# OSHChip_CMSIS_DAP_V1_0.net
KiCad netlist of a schematic drawn in Altium Designer
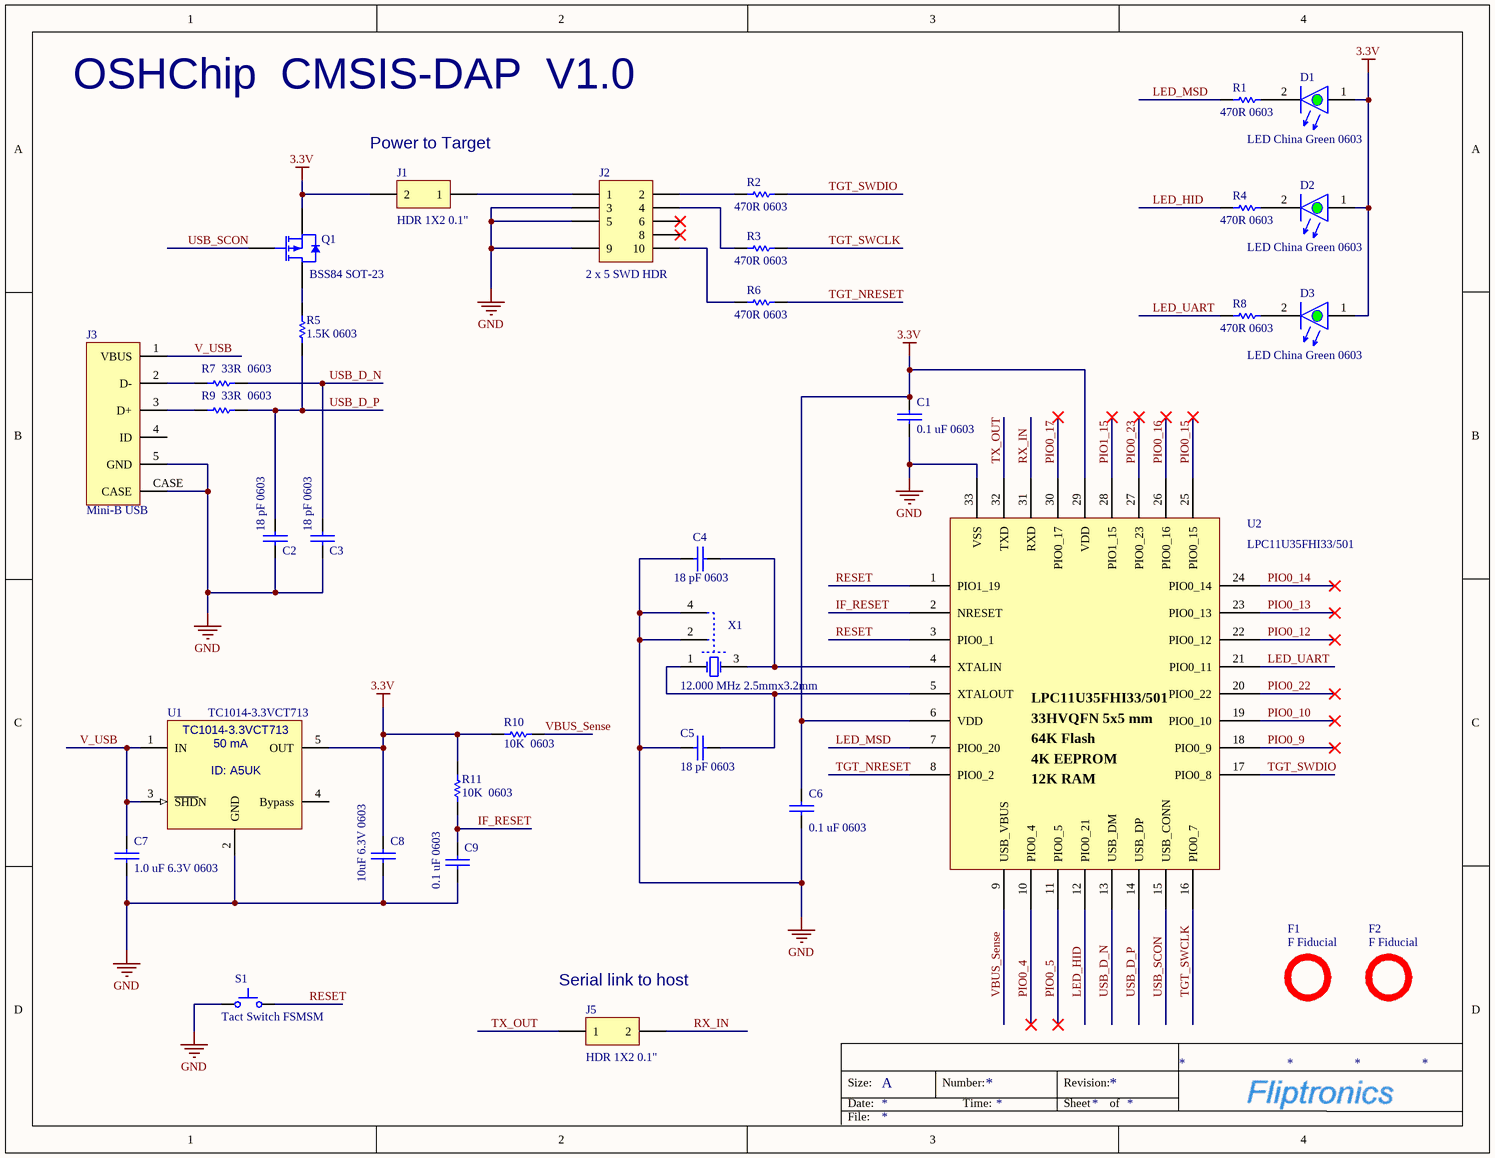
[diagram p0: OSHChip_CMSIS_DAP_V1.0.SchDoc]

(export (version "E")
  (design (tool "Eeschema 10.0.6"))
  (components
    (comp (ref "C1")
      (value "0.1 uF 0603")
      (footprint "Footprints:0603 Cap")
      (description "0.1 uF 16V 10% X7R 0603")
      (fields
        (field (name "PART NUMBER") "CC0603KRX7R7BB104")
        (field (name "LATESTREVISIONNOTE") "Created by PMF")
      )
      (libsource (lib "OSHChip_V1.0") (part "C 0.1 uF 16V 10% X7R 0603"))
    )
    (comp (ref "C2")
      (value "18 pF 0603")
      (footprint "Footprints:0603 Cap")
      (description "Capacitor 18 pF 0603  50V  NP0  5%")
      (fields
        (field (name "PART NUMBER") "CL10C180JB8NNNC")
        (field (name "LATESTREVISIONNOTE") "Created by PMF")
      )
      (libsource (lib "OSHChip_V1.0") (part "C 18 pF 0603  50V  NP0  5%"))
    )
    (comp (ref "C3")
      (value "18 pF 0603")
      (footprint "Footprints:0603 Cap")
      (description "Capacitor 18 pF 0603  50V  NP0  5%")
      (fields
        (field (name "PART NUMBER") "CL10C180JB8NNNC")
        (field (name "LATESTREVISIONNOTE") "Created by PMF")
      )
      (libsource (lib "OSHChip_V1.0") (part "C 18 pF 0603  50V  NP0  5%"))
    )
    (comp (ref "C4")
      (value "18 pF 0603")
      (footprint "Footprints:0603 Cap")
      (description "Capacitor 18 pF 0603  50V  NP0  5%")
      (fields
        (field (name "PART NUMBER") "CL10C180JB8NNNC")
        (field (name "LATESTREVISIONNOTE") "Created by PMF")
      )
      (libsource (lib "OSHChip_V1.0") (part "C 18 pF 0603  50V  NP0  5%"))
    )
    (comp (ref "C5")
      (value "18 pF 0603")
      (footprint "Footprints:0603 Cap")
      (description "Capacitor 18 pF 0603  50V  NP0  5%")
      (fields
        (field (name "PART NUMBER") "CL10C180JB8NNNC")
        (field (name "LATESTREVISIONNOTE") "Created by PMF")
      )
      (libsource (lib "OSHChip_V1.0") (part "C 18 pF 0603  50V  NP0  5%"))
    )
    (comp (ref "C6")
      (value "0.1 uF 0603")
      (footprint "Footprints:0603 Cap")
      (description "0.1 uF 16V 10% X7R 0603")
      (fields
        (field (name "PART NUMBER") "CC0603KRX7R7BB104")
        (field (name "LATESTREVISIONNOTE") "Created by PMF")
      )
      (libsource (lib "OSHChip_V1.0") (part "C 0.1 uF 16V 10% X7R 0603"))
    )
    (comp (ref "C7")
      (value "1.0 uF 6.3V 0603")
      (footprint "Footprints:0603 Cap")
      (description "Capacitor 1.0 uF 6.3V 10% X7R 0603")
      (fields
        (field (name "PART NUMBER") "CL10B105KQ8NNNC")
        (field (name "LATESTREVISIONNOTE") "Created by PMF")
      )
      (libsource (lib "OSHChip_V1.0") (part "C 1.0 uF 6.3V 10% X7R 0603"))
    )
    (comp (ref "C8")
      (value "10uF 6.3V 0603")
      (footprint "Footprints:0603 Cap")
      (description "Capacitor 10uF 0603 6.3V 20% X5R")
      (fields
        (field (name "PART NUMBER") "CL10A106MQ8NNNC")
        (field (name "LATESTREVISIONNOTE") "Created by PMF")
      )
      (libsource (lib "OSHChip_V1.0") (part "C 10uF 0603 6.3V 20% X5R"))
    )
    (comp (ref "C9")
      (value "0.1 uF 0603")
      (footprint "Footprints:0603 Cap")
      (description "0.1 uF 16V 10% X7R 0603")
      (fields
        (field (name "PART NUMBER") "CC0603KRX7R7BB104")
        (field (name "LATESTREVISIONNOTE") "Created by PMF")
      )
      (libsource (lib "OSHChip_V1.0") (part "C 0.1 uF 16V 10% X7R 0603"))
    )
    (comp (ref "D1")
      (value "LED China Green 0603")
      (footprint "0603_LED")
      (description "LED Green 0603")
      (fields
        (field (name "PART NUMBER") "ChinaLED_Green")
        (field (name "LATESTREVISIONNOTE") "Created by PMF")
      )
      (libsource (lib "OSHChip_V1.0") (part "D LED LED_China_Green_0603"))
    )
    (comp (ref "D2")
      (value "LED China Green 0603")
      (footprint "0603_LED")
      (description "LED Green 0603")
      (fields
        (field (name "PART NUMBER") "ChinaLED_Green")
        (field (name "LATESTREVISIONNOTE") "Created by PMF")
      )
      (libsource (lib "OSHChip_V1.0") (part "D LED LED_China_Green_0603"))
    )
    (comp (ref "D3")
      (value "LED China Green 0603")
      (footprint "0603_LED")
      (description "LED Green 0603")
      (fields
        (field (name "PART NUMBER") "ChinaLED_Green")
        (field (name "LATESTREVISIONNOTE") "Created by PMF")
      )
      (libsource (lib "OSHChip_V1.0") (part "D LED LED_China_Green_0603"))
    )
    (comp (ref "F1")
      (value "F Fiducial")
      (footprint "footprints:Fiducial Dot")
      (description "Fiducial")
      (fields
        (field (name "1 MANUFACTURE A PART NUMBER") "PCB_Artwork")
        (field (name "LATESTREVISIONNOTE") "Created by PMF")
        (field (name "PUBLISHER") "Fliptronics")
      )
      (libsource (lib "*") (part "F Fiducial"))
    )
    (comp (ref "F2")
      (value "F Fiducial")
      (footprint "footprints:Fiducial Dot")
      (description "Fiducial")
      (fields
        (field (name "1 MANUFACTURE A PART NUMBER") "PCB_Artwork")
        (field (name "LATESTREVISIONNOTE") "Created by PMF")
        (field (name "PUBLISHER") "Fliptronics")
      )
      (libsource (lib "*") (part "F Fiducial"))
    )
    (comp (ref "J1")
      (value "HDR 1X2 0.1\"")
      (footprint "HDR_2X1_2MM54")
      (description "Header 1X2, 2.54 mm pitch")
      (fields (field (name "PART NUMBER") "M20-9990246") (field (name "LATESTREVISIONNOTE") "Created by PMF"))
      (libsource (lib "") (part "J Header 1X2, 2.54 mm pitch_1"))
    )
    (comp (ref "J2")
      (value "2 x 5 SWD HDR")
      (footprint "Footprints:HDR_2x5_1.27mm-Through_Hole_SWD No Shroud")
      (description "FTSH-105-01-L-D through hole, No Key, No shroud")
      (fields
        (field (name "PART NUMBER") "FTSH-105-01-L-D")
        (field (name "LATESTREVISIONNOTE") "Created by PMF")
      )
      (libsource (lib "OSHChip_V1.0") (part "J Header 5X2 J-Link Lite   FTSH-105-01-L-D through hole, No Key, No shroud"))
    )
    (comp (ref "J3")
      (value "Mini-B USB")
      (footprint "footprints:USB_Mini-B")
      (description "USB 2.0, Right Angle, SMT, B Type, Receptacle, 5 Position, Black")
      (fields
        (field (name "PART NUMBER") "690-005-299-043")
        (field (name "LATESTREVISIONNOTE") "Created by PMF")
      )
      (libsource (lib "OSHChip_V1.0") (part "J Mini-B USB 690-005-299-043 With alignment pins"))
    )
    (comp (ref "J5")
      (value "HDR 1X2 0.1\"")
      (footprint "HDR_2X1_2MM54")
      (description "Header 1X2, 2.54 mm pitch")
      (fields (field (name "PART NUMBER") "M20-9990246") (field (name "LATESTREVISIONNOTE") "Created by PMF"))
      (libsource (lib "OSHChip_V1.0") (part "J Header 1X2, 2.54 mm pitch"))
    )
    (comp (ref "Q1")
      (value "BSS84 SOT-23")
      (footprint "Footprints:SOT23-123")
      (description "P-channel Enhancement Mode Vertical D-MOSFET")
      (fields (field (name "PART NUMBER") "BSS84,215"))
      (libsource (lib "OSHChip_V1.0") (part "Q BSS84"))
    )
    (comp (ref "R1")
      (value "470R 0603")
      (footprint "Footprints:0603 Res")
      (description "Resistor 470R 0603 1/10 W 1%")
      (fields
        (field (name "PART NUMBER") "RC1608F471CS")
        (field (name "LATESTREVISIONNOTE") "Created by PMF")
      )
      (libsource (lib "OSHChip_V1.0") (part "R 470R 0603 1/10 W 1%"))
    )
    (comp (ref "R2")
      (value "470R 0603")
      (footprint "Footprints:0603 Res")
      (description "Resistor 470R 0603 1/10 W 1%")
      (fields
        (field (name "PART NUMBER") "RC1608F471CS")
        (field (name "LATESTREVISIONNOTE") "Created by PMF")
      )
      (libsource (lib "OSHChip_V1.0") (part "R 470R 0603 1/10 W 1%"))
    )
    (comp (ref "R3")
      (value "470R 0603")
      (footprint "Footprints:0603 Res")
      (description "Resistor 470R 0603 1/10 W 1%")
      (fields
        (field (name "PART NUMBER") "RC1608F471CS")
        (field (name "LATESTREVISIONNOTE") "Created by PMF")
      )
      (libsource (lib "OSHChip_V1.0") (part "R 470R 0603 1/10 W 1%"))
    )
    (comp (ref "R4")
      (value "470R 0603")
      (footprint "Footprints:0603 Res")
      (description "Resistor 470R 0603 1/10 W 1%")
      (fields
        (field (name "PART NUMBER") "RC1608F471CS")
        (field (name "LATESTREVISIONNOTE") "Created by PMF")
      )
      (libsource (lib "OSHChip_V1.0") (part "R 470R 0603 1/10 W 1%"))
    )
    (comp (ref "R5")
      (value "1.5K 0603")
      (footprint "Footprints:0603 Res")
      (description "Resistor 1.5K 0402 1/10 W 1%")
      (fields
        (field (name "PART NUMBER") "RC0603FR-071K5L")
        (field (name "LATESTREVISIONNOTE") "Created by PMF")
      )
      (libsource (lib "OSHChip_V1.0") (part "R 1.5K 0603 1/10 W 1%"))
    )
    (comp (ref "R6")
      (value "470R 0603")
      (footprint "Footprints:0603 Res")
      (description "Resistor 470R 0603 1/10 W 1%")
      (fields
        (field (name "PART NUMBER") "RC1608F471CS")
        (field (name "LATESTREVISIONNOTE") "Created by PMF")
      )
      (libsource (lib "OSHChip_V1.0") (part "R 470R 0603 1/10 W 1%"))
    )
    (comp (ref "R7")
      (value "33R  0603")
      (footprint "Footprints:0603 Res")
      (description "Resistor 33R 0603 1/10 W 1%")
      (fields
        (field (name "PART NUMBER") "MCR03ERTF33R0")
        (field (name "LATESTREVISIONNOTE") "Created by PMF")
      )
      (libsource (lib "OSHChip_V1.0") (part "R 33R 0603 1/10 W 1%"))
    )
    (comp (ref "R8")
      (value "470R 0603")
      (footprint "Footprints:0603 Res")
      (description "Resistor 470R 0603 1/10 W 1%")
      (fields
        (field (name "PART NUMBER") "RC1608F471CS")
        (field (name "LATESTREVISIONNOTE") "Created by PMF")
      )
      (libsource (lib "OSHChip_V1.0") (part "R 470R 0603 1/10 W 1%"))
    )
    (comp (ref "R9")
      (value "33R  0603")
      (footprint "Footprints:0603 Res")
      (description "Resistor 33R 0603 1/10 W 1%")
      (fields
        (field (name "PART NUMBER") "MCR03ERTF33R0")
        (field (name "LATESTREVISIONNOTE") "Created by PMF")
      )
      (libsource (lib "OSHChip_V1.0") (part "R 33R 0603 1/10 W 1%"))
    )
    (comp (ref "R10")
      (value "10K  0603")
      (footprint "Footprints:0603 Res")
      (description "Resistor 10K 0603 1/10 W 1%")
      (fields
        (field (name "PART NUMBER") "MCR03ERTF1002")
        (field (name "LATESTREVISIONNOTE") "Created by PMF")
      )
      (libsource (lib "OSHChip_V1.0") (part "R 10K 0603 1/10 W 1%"))
    )
    (comp (ref "R11")
      (value "10K  0603")
      (footprint "Footprints:0603 Res")
      (description "Resistor 10K 0603 1/10 W 1%")
      (fields
        (field (name "PART NUMBER") "MCR03ERTF1002")
        (field (name "LATESTREVISIONNOTE") "Created by PMF")
      )
      (libsource (lib "OSHChip_V1.0") (part "R 10K 0603 1/10 W 1%"))
    )
    (comp (ref "S1")
      (value "Tact Switch FSMSM")
      (footprint "Footprints:FSMSM Tact Switch")
      (description "6 x 3.5 mm   Tact Switch")
      (fields (field (name "PART NUMBER") "FSMSMTR") (field (name "LATESTREVISIONNOTE") "Created by PMF"))
      (libsource (lib "OSHChip_V1.0") (part "S FSMSM 6 x 3.5 mm   Tact Switch"))
    )
    (comp (ref "U1")
      (value "TC1014-3.3VCT713")
      (footprint "Footprints:SOT23-5AL")
      (description "3.3V 50mA LDO")
      (fields (field (name "LATESTREVISIONNOTE") "Created by PMF"))
      (libsource (lib "OSHChip_V1.0") (part "U TC1014-3.3VCT713"))
    )
    (comp (ref "U2")
      (value "LPC11U35FHI33/501")
      (footprint "Footprints:LPC11U35 QFN32 footprint")
      (description "LPC11U35FHI33/501 ARM M0 64KB FLASH 33HVQFN")
      (fields (field (name "LATESTREVISIONNOTE") "Created by PMF"))
      (libsource (lib "OSHChip_V1.0") (part "U LPC11U35FHI33/501"))
    )
    (comp (ref "X1")
      (value "12.000 MHz 2.5mmx3.2mm")
      (footprint "footprints:NX3225SA - High Density")
      (description "12MHz")
      (fields
        (field (name "PART NUMBER") "CX3225GB12000D0HEQCC")
        (field (name "LATESTREVISIONNOTE") "Created by PMF")
      )
      (libsource (lib "OSHChip_V1.0") (part "X 12MHz, 2.5mmx3.2mm 30ppm 8 pF"))
    )
  )
  (nets
    (net (code "1") (name "/IF_RESET") (class "Default")
      (node (ref "C9") (pin "2") (pinfunction "2_2") (pintype "passive"))
      (node (ref "R11") (pin "1") (pinfunction "1_1") (pintype "passive"))
      (node (ref "U2") (pin "2") (pinfunction "NRESET_2") (pintype "passive"))
    )
    (net (code "2") (name "/LED_HID") (class "Default")
      (node (ref "R4") (pin "1") (pinfunction "1_1") (pintype "passive"))
      (node (ref "U2") (pin "12") (pinfunction "PIO0_21_12") (pintype "passive"))
    )
    (net (code "3") (name "/LED_MSD") (class "Default")
      (node (ref "R1") (pin "1") (pinfunction "1_1") (pintype "passive"))
      (node (ref "U2") (pin "7") (pinfunction "PIO0_20_7") (pintype "passive"))
    )
    (net (code "4") (name "/LED_UART") (class "Default")
      (node (ref "R8") (pin "1") (pinfunction "1_1") (pintype "passive"))
      (node (ref "U2") (pin "21") (pinfunction "PIO0_11_21") (pintype "passive"))
    )
    (net (code "5") (name "/PIO0_4") (class "Default")
      (node (ref "U2") (pin "10") (pinfunction "PIO0_4_10") (pintype "passive+no_connect"))
    )
    (net (code "6") (name "/PIO0_5") (class "Default")
      (node (ref "U2") (pin "11") (pinfunction "PIO0_5_11") (pintype "passive+no_connect"))
    )
    (net (code "7") (name "/PIO0_9") (class "Default")
      (node (ref "U2") (pin "18") (pinfunction "PIO0_9_18") (pintype "passive+no_connect"))
    )
    (net (code "8") (name "/PIO0_10") (class "Default")
      (node (ref "U2") (pin "19") (pinfunction "PIO0_10_19") (pintype "passive+no_connect"))
    )
    (net (code "9") (name "/PIO0_12") (class "Default")
      (node (ref "U2") (pin "22") (pinfunction "PIO0_12_22") (pintype "passive+no_connect"))
    )
    (net (code "10") (name "/PIO0_13") (class "Default")
      (node (ref "U2") (pin "23") (pinfunction "PIO0_13_23") (pintype "passive+no_connect"))
    )
    (net (code "11") (name "/PIO0_14") (class "Default")
      (node (ref "U2") (pin "24") (pinfunction "PIO0_14_24") (pintype "passive+no_connect"))
    )
    (net (code "12") (name "/PIO0_15") (class "Default")
      (node (ref "U2") (pin "25") (pinfunction "PIO0_15_25") (pintype "passive+no_connect"))
    )
    (net (code "13") (name "/PIO0_16") (class "Default")
      (node (ref "U2") (pin "26") (pinfunction "PIO0_16_26") (pintype "passive+no_connect"))
    )
    (net (code "14") (name "/PIO0_17") (class "Default")
      (node (ref "U2") (pin "30") (pinfunction "PIO0_17_30") (pintype "passive+no_connect"))
    )
    (net (code "15") (name "/PIO0_22") (class "Default")
      (node (ref "U2") (pin "20") (pinfunction "PIO0_22_20") (pintype "passive+no_connect"))
    )
    (net (code "16") (name "/PIO0_23") (class "Default")
      (node (ref "U2") (pin "27") (pinfunction "PIO0_23_27") (pintype "passive+no_connect"))
    )
    (net (code "17") (name "/PIO1_15") (class "Default")
      (node (ref "U2") (pin "28") (pinfunction "PIO1_15_28") (pintype "passive+no_connect"))
    )
    (net (code "18") (name "/RESET") (class "Default")
      (node (ref "S1") (pin "2") (pinfunction "2_2") (pintype "passive"))
      (node (ref "U2") (pin "1") (pinfunction "PIO1_19_1") (pintype "passive"))
      (node (ref "U2") (pin "3") (pinfunction "PIO0_1_3") (pintype "passive"))
    )
    (net (code "19") (name "/RX_IN") (class "Default")
      (node (ref "J5") (pin "2") (pinfunction "2_2") (pintype "passive"))
      (node (ref "U2") (pin "31") (pinfunction "RXD_31") (pintype "passive"))
    )
    (net (code "20") (name "/TGT_NRESET") (class "Default")
      (node (ref "R6") (pin "2") (pinfunction "2_2") (pintype "passive"))
      (node (ref "U2") (pin "8") (pinfunction "PIO0_2_8") (pintype "passive"))
    )
    (net (code "21") (name "/TGT_SWCLK") (class "Default")
      (node (ref "R3") (pin "2") (pinfunction "2_2") (pintype "passive"))
      (node (ref "U2") (pin "16") (pinfunction "PIO0_7_16") (pintype "passive"))
    )
    (net (code "22") (name "/TGT_SWDIO") (class "Default")
      (node (ref "R2") (pin "2") (pinfunction "2_2") (pintype "passive"))
      (node (ref "U2") (pin "17") (pinfunction "PIO0_8_17") (pintype "passive"))
    )
    (net (code "23") (name "/TX_OUT") (class "Default")
      (node (ref "J5") (pin "1") (pinfunction "1_1") (pintype "passive"))
      (node (ref "U2") (pin "32") (pinfunction "TXD_32") (pintype "passive"))
    )
    (net (code "24") (name "/USB_D_N") (class "Default")
      (node (ref "C3") (pin "2") (pinfunction "2_2") (pintype "passive"))
      (node (ref "R7") (pin "2") (pinfunction "2_2") (pintype "passive"))
      (node (ref "U2") (pin "13") (pinfunction "USB_DM_13") (pintype "passive"))
    )
    (net (code "25") (name "/USB_D_P") (class "Default")
      (node (ref "C2") (pin "2") (pinfunction "2_2") (pintype "passive"))
      (node (ref "R5") (pin "1") (pinfunction "1_1") (pintype "passive"))
      (node (ref "R9") (pin "2") (pinfunction "2_2") (pintype "passive"))
      (node (ref "U2") (pin "14") (pinfunction "USB_DP_14") (pintype "passive"))
    )
    (net (code "26") (name "/USB_SCON") (class "Default")
      (node (ref "Q1") (pin "1") (pinfunction "G_1") (pintype "passive"))
      (node (ref "U2") (pin "15") (pinfunction "USB_CONN_15") (pintype "passive"))
    )
    (net (code "27") (name "/VBUS_Sense") (class "Default")
      (node (ref "R10") (pin "1") (pinfunction "1_1") (pintype "passive"))
      (node (ref "U2") (pin "9") (pinfunction "USB_VBUS_9") (pintype "passive"))
    )
    (net (code "28") (name "/V_USB") (class "Default")
      (node (ref "C7") (pin "2") (pinfunction "2_2") (pintype "passive"))
      (node (ref "J3") (pin "1") (pinfunction "VBUS_1") (pintype "power_in"))
      (node (ref "U1") (pin "1") (pinfunction "IN_1") (pintype "power_in"))
      (node (ref "U1") (pin "3") (pinfunction "~{SHD}N_3") (pintype "input"))
    )
    (net (code "29") (name "3.3V") (class "Default")
      (node (ref "C1") (pin "2") (pinfunction "2_2") (pintype "passive"))
      (node (ref "C6") (pin "2") (pinfunction "2_2") (pintype "passive"))
      (node (ref "C8") (pin "2") (pinfunction "2_2") (pintype "passive"))
      (node (ref "D1") (pin "1") (pinfunction "1_1") (pintype "passive"))
      (node (ref "D2") (pin "1") (pinfunction "1_1") (pintype "passive"))
      (node (ref "D3") (pin "1") (pinfunction "1_1") (pintype "passive"))
      (node (ref "J1") (pin "2") (pinfunction "2_2") (pintype "passive"))
      (node (ref "Q1") (pin "2") (pinfunction "S_2") (pintype "passive"))
      (node (ref "R10") (pin "2") (pinfunction "2_2") (pintype "passive"))
      (node (ref "R11") (pin "2") (pinfunction "2_2") (pintype "passive"))
      (node (ref "U1") (pin "5") (pinfunction "OUT_5") (pintype "power_in"))
      (node (ref "U2") (pin "29") (pinfunction "VDD_29") (pintype "passive"))
      (node (ref "U2") (pin "6") (pinfunction "VDD_6") (pintype "passive"))
    )
    (net (code "30") (name "GND") (class "Default")
      (node (ref "C1") (pin "1") (pinfunction "1_1") (pintype "passive"))
      (node (ref "C2") (pin "1") (pinfunction "1_1") (pintype "passive"))
      (node (ref "C3") (pin "1") (pinfunction "1_1") (pintype "passive"))
      (node (ref "C4") (pin "2") (pinfunction "2_2") (pintype "passive"))
      (node (ref "C5") (pin "2") (pinfunction "2_2") (pintype "passive"))
      (node (ref "C6") (pin "1") (pinfunction "1_1") (pintype "passive"))
      (node (ref "C7") (pin "1") (pinfunction "1_1") (pintype "passive"))
      (node (ref "C8") (pin "1") (pinfunction "1_1") (pintype "passive"))
      (node (ref "C9") (pin "1") (pinfunction "1_1") (pintype "passive"))
      (node (ref "J2") (pin "3") (pinfunction "3_3") (pintype "passive"))
      (node (ref "J2") (pin "5") (pinfunction "5_5") (pintype "passive"))
      (node (ref "J2") (pin "9") (pinfunction "9_9") (pintype "passive"))
      (node (ref "J3") (pin "5") (pinfunction "GND_5") (pintype "power_in"))
      (node (ref "J3") (pin "CASE") (pinfunction "CASE_CASE") (pintype "power_in"))
      (node (ref "S1") (pin "1") (pinfunction "1_1") (pintype "passive"))
      (node (ref "U1") (pin "2") (pinfunction "GND_2") (pintype "power_in"))
      (node (ref "U2") (pin "33") (pinfunction "VSS_33") (pintype "passive"))
      (node (ref "X1") (pin "2") (pinfunction "nc_2_2") (pintype "passive"))
      (node (ref "X1") (pin "4") (pinfunction "nc_4_4") (pintype "passive"))
    )
    (net (code "31") (name "Net-(D1-Pad2)") (class "Default")
      (node (ref "D1") (pin "2") (pinfunction "2_2") (pintype "passive"))
      (node (ref "R1") (pin "2") (pinfunction "2_2") (pintype "passive"))
    )
    (net (code "32") (name "Net-(D2-Pad2)") (class "Default")
      (node (ref "D2") (pin "2") (pinfunction "2_2") (pintype "passive"))
      (node (ref "R4") (pin "2") (pinfunction "2_2") (pintype "passive"))
    )
    (net (code "33") (name "Net-(D3-Pad2)") (class "Default")
      (node (ref "D3") (pin "2") (pinfunction "2_2") (pintype "passive"))
      (node (ref "R8") (pin "2") (pinfunction "2_2") (pintype "passive"))
    )
    (net (code "34") (name "Net-(J1-Pad1)") (class "Default")
      (node (ref "J1") (pin "1") (pinfunction "1_1") (pintype "passive"))
      (node (ref "J2") (pin "1") (pinfunction "1_1") (pintype "passive"))
    )
    (net (code "35") (name "Net-(J2-Pad2)") (class "Default")
      (node (ref "J2") (pin "2") (pinfunction "2_2") (pintype "passive"))
      (node (ref "R2") (pin "1") (pinfunction "1_1") (pintype "passive"))
    )
    (net (code "36") (name "Net-(J2-Pad4)") (class "Default")
      (node (ref "J2") (pin "4") (pinfunction "4_4") (pintype "passive"))
      (node (ref "R3") (pin "1") (pinfunction "1_1") (pintype "passive"))
    )
    (net (code "37") (name "Net-(J2-Pad10)") (class "Default")
      (node (ref "J2") (pin "10") (pinfunction "10_10") (pintype "passive"))
      (node (ref "R6") (pin "1") (pinfunction "1_1") (pintype "passive"))
    )
    (net (code "38") (name "Net-(J3-D+)") (class "Default")
      (node (ref "J3") (pin "3") (pinfunction "D+_3") (pintype "passive"))
      (node (ref "R9") (pin "1") (pinfunction "1_1") (pintype "passive"))
    )
    (net (code "39") (name "Net-(J3-D-)") (class "Default")
      (node (ref "J3") (pin "2") (pinfunction "D-_2") (pintype "passive"))
      (node (ref "R7") (pin "1") (pinfunction "1_1") (pintype "passive"))
    )
    (net (code "40") (name "Net-(Q1-D)") (class "Default")
      (node (ref "Q1") (pin "3") (pinfunction "D_3") (pintype "passive"))
      (node (ref "R5") (pin "2") (pinfunction "2_2") (pintype "passive"))
    )
    (net (code "41") (name "Net-(U2-XTALIN)") (class "Default")
      (node (ref "C4") (pin "1") (pinfunction "1_1") (pintype "passive"))
      (node (ref "U2") (pin "4") (pinfunction "XTALIN_4") (pintype "passive"))
      (node (ref "X1") (pin "3") (pinfunction "OSC2_3") (pintype "passive"))
    )
    (net (code "42") (name "Net-(U2-XTALOUT)") (class "Default")
      (node (ref "C5") (pin "1") (pinfunction "1_1") (pintype "passive"))
      (node (ref "U2") (pin "5") (pinfunction "XTALOUT_5") (pintype "passive"))
      (node (ref "X1") (pin "1") (pinfunction "OSC1_1") (pintype "passive"))
    )
    (net (code "43") (name "unconnected-(J2-Pad6)") (class "Default")
      (node (ref "J2") (pin "6") (pinfunction "6_6") (pintype "passive+no_connect"))
    )
    (net (code "44") (name "unconnected-(J2-Pad8)") (class "Default")
      (node (ref "J2") (pin "8") (pinfunction "8_8") (pintype "passive+no_connect"))
    )
    (net (code "45") (name "unconnected-(J3-ID-Pad4)") (class "Default")
      (node (ref "J3") (pin "4") (pinfunction "ID_4") (pintype "passive"))
    )
    (net (code "46") (name "unconnected-(U1-Bypass-Pad4)") (class "Default")
      (node (ref "U1") (pin "4") (pinfunction "Bypass_4") (pintype "passive"))
    )
  )
)
